# tailSensors.net
KiCad netlist of a schematic drawn in Altium Designer
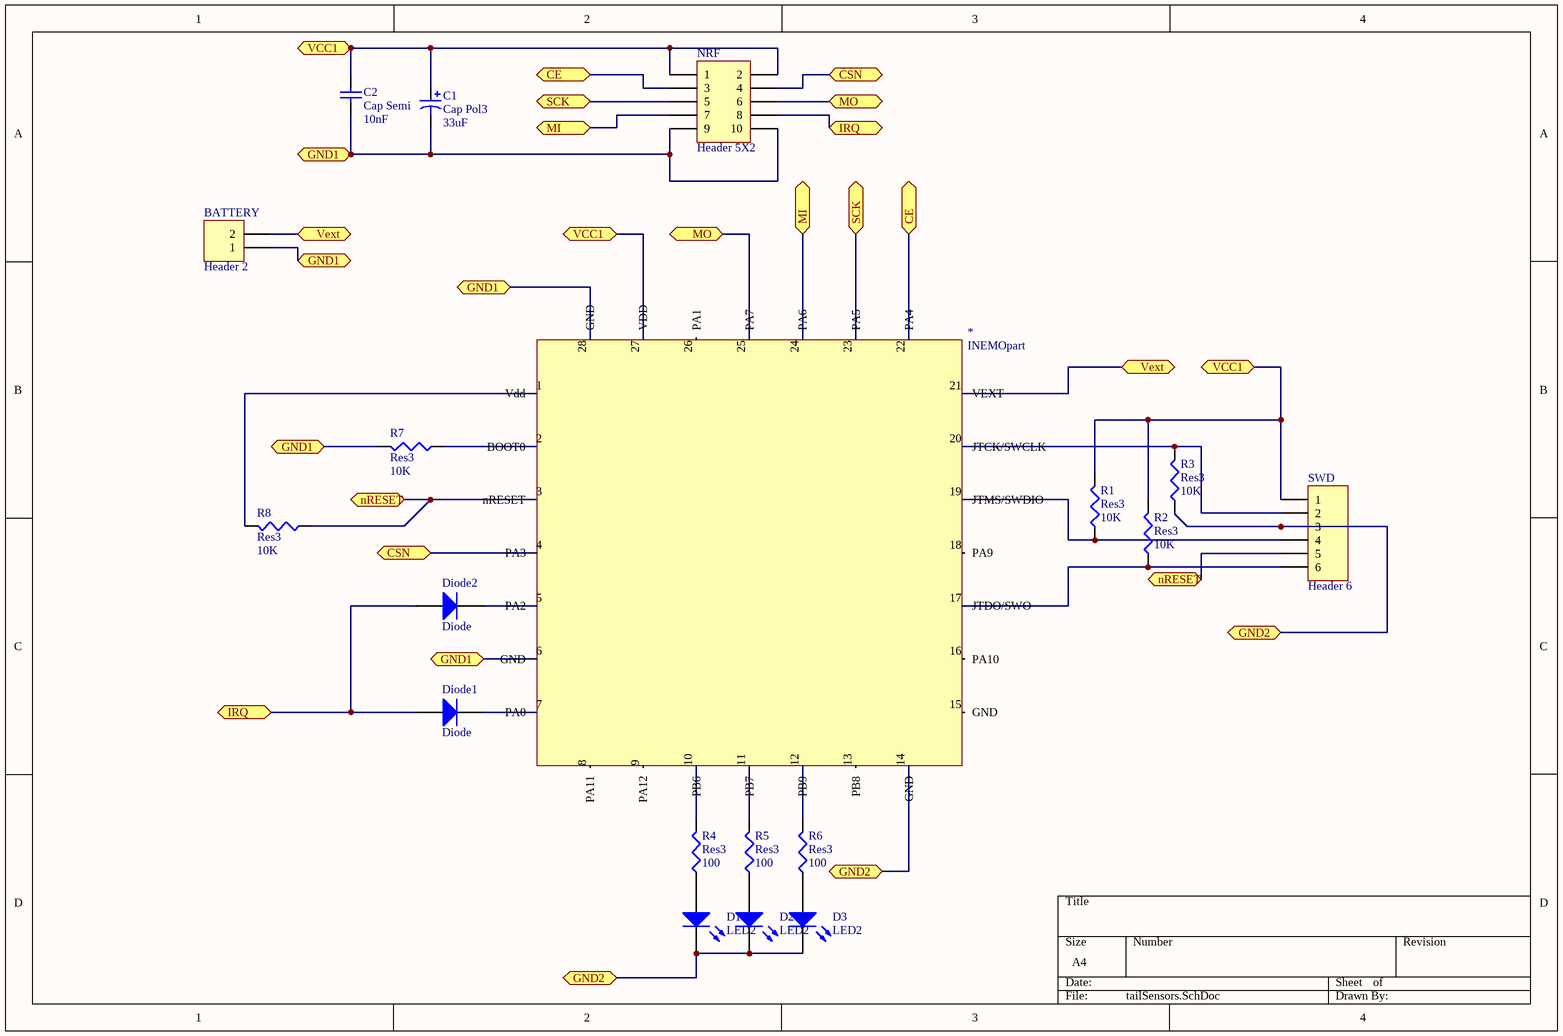
[diagram p0: tailSensors.SchDoc]

(export (version "E")
  (design (tool "Eeschema 10.0.6"))
  (components
    (comp (ref "*")
      (value "INEMOpart")
      (footprint "INEMO - duplicate3")
      (libsource (lib "INEMOLibrary") (part "Component_1"))
    )
    (comp (ref "BATTERY")
      (value "Header 2")
      (footprint "HDR1X2")
      (description "Header, 2-Pin")
      (fields (field (name "PUBLISHER") "Altium Limited"))
      (libsource (lib "Miscellaneous Connectors") (part "Header 2"))
    )
    (comp (ref "C1")
      (value "Cap Pol3")
      (footprint "C0805")
      (description "Polarized Capacitor (Surface Mount)")
      (fields (field (name "ALTIUM_VALUE") "33uF") (field (name "PUBLISHER") "Altium Limited"))
      (libsource (lib "Miscellaneous Devices") (part "Cap Pol3"))
    )
    (comp (ref "C2")
      (value "Cap Semi")
      (footprint "C1206")
      (description "Capacitor (Semiconductor SIM Model)")
      (fields (field (name "ALTIUM_VALUE") "10nF") (field (name "PUBLISHER") "Altium Limited"))
      (libsource (lib "Miscellaneous Devices") (part "Cap Semi"))
    )
    (comp (ref "D1")
      (value "LED2")
      (footprint "3.2X1.6X1.1")
      (description "Typical RED, GREEN, YELLOW, AMBER GaAs LED")
      (fields (field (name "PUBLISHER") "Altium Limited"))
      (libsource (lib "Miscellaneous Devices") (part "LED2"))
    )
    (comp (ref "D2")
      (value "LED2")
      (footprint "3.2X1.6X1.1")
      (description "Typical RED, GREEN, YELLOW, AMBER GaAs LED")
      (fields (field (name "PUBLISHER") "Altium Limited"))
      (libsource (lib "Miscellaneous Devices") (part "LED2"))
    )
    (comp (ref "D3")
      (value "LED2")
      (footprint "3.2X1.6X1.1")
      (description "Typical RED, GREEN, YELLOW, AMBER GaAs LED")
      (fields (field (name "PUBLISHER") "Altium Limited"))
      (libsource (lib "Miscellaneous Devices") (part "LED2"))
    )
    (comp (ref "Diode1")
      (value "Diode")
      (footprint "J1-0603")
      (description "Default Diode")
      (fields (field (name "PUBLISHER") "Altium Limited"))
      (libsource (lib "Miscellaneous Devices") (part "Diode"))
    )
    (comp (ref "Diode2")
      (value "Diode")
      (footprint "J1-0603")
      (description "Default Diode")
      (fields (field (name "PUBLISHER") "Altium Limited"))
      (libsource (lib "Miscellaneous Devices") (part "Diode"))
    )
    (comp (ref "NRF")
      (value "Header 5X2")
      (footprint "HDR2X5")
      (description "Header, 5-Pin, Dual row")
      (fields (field (name "PUBLISHER") "Altium Limited"))
      (libsource (lib "Miscellaneous Connectors") (part "Header 5X2"))
    )
    (comp (ref "R1")
      (value "Res3")
      (footprint "J1-0603")
      (description "Resistor")
      (fields (field (name "ALTIUM_VALUE") "10K") (field (name "PUBLISHER") "Altium Limited"))
      (libsource (lib "Miscellaneous Devices") (part "Res3"))
    )
    (comp (ref "R2")
      (value "Res3")
      (footprint "J1-0603")
      (description "Resistor")
      (fields (field (name "ALTIUM_VALUE") "10K") (field (name "PUBLISHER") "Altium Limited"))
      (libsource (lib "Miscellaneous Devices") (part "Res3"))
    )
    (comp (ref "R3")
      (value "Res3")
      (footprint "J1-0603")
      (description "Resistor")
      (fields (field (name "ALTIUM_VALUE") "10K") (field (name "PUBLISHER") "Altium Limited"))
      (libsource (lib "Miscellaneous Devices") (part "Res3"))
    )
    (comp (ref "R4")
      (value "Res3")
      (footprint "J1-0603")
      (description "Resistor")
      (fields (field (name "ALTIUM_VALUE") "100") (field (name "PUBLISHER") "Altium Limited"))
      (libsource (lib "Miscellaneous Devices") (part "Res3"))
    )
    (comp (ref "R5")
      (value "Res3")
      (footprint "J1-0603")
      (description "Resistor")
      (fields (field (name "ALTIUM_VALUE") "100") (field (name "PUBLISHER") "Altium Limited"))
      (libsource (lib "Miscellaneous Devices") (part "Res3"))
    )
    (comp (ref "R6")
      (value "Res3")
      (footprint "J1-0603")
      (description "Resistor")
      (fields (field (name "ALTIUM_VALUE") "100") (field (name "PUBLISHER") "Altium Limited"))
      (libsource (lib "Miscellaneous Devices") (part "Res3"))
    )
    (comp (ref "R7")
      (value "Res3")
      (footprint "J1-0603")
      (description "Resistor")
      (fields (field (name "ALTIUM_VALUE") "10K") (field (name "PUBLISHER") "Altium Limited"))
      (libsource (lib "Miscellaneous Devices") (part "Res3"))
    )
    (comp (ref "R8")
      (value "Res3")
      (footprint "J1-0603")
      (description "Resistor")
      (fields (field (name "ALTIUM_VALUE") "10K") (field (name "PUBLISHER") "Altium Limited"))
      (libsource (lib "Miscellaneous Devices") (part "Res3"))
    )
    (comp (ref "SWD")
      (value "Header 6")
      (footprint "HDR1X6")
      (description "Header, 6-Pin")
      (fields (field (name "PUBLISHER") "Altium Limited"))
      (libsource (lib "Miscellaneous Connectors") (part "Header 6"))
    )
  )
  (nets
    (net (code "1") (name "/CE") (class "Default")
      (node (ref "*") (pin "22") (pinfunction "PA4_22") (pintype "passive"))
      (node (ref "NRF") (pin "3") (pinfunction "3_3") (pintype "passive"))
    )
    (net (code "2") (name "/CSN") (class "Default")
      (node (ref "*") (pin "4") (pinfunction "PA3_4") (pintype "passive"))
      (node (ref "NRF") (pin "4") (pinfunction "4_4") (pintype "passive"))
    )
    (net (code "3") (name "/GND1") (class "Default")
      (node (ref "*") (pin "28") (pinfunction "GND_28") (pintype "passive"))
      (node (ref "*") (pin "6") (pinfunction "GND_6") (pintype "passive"))
      (node (ref "BATTERY") (pin "1") (pinfunction "1_1") (pintype "passive"))
      (node (ref "C1") (pin "2") (pinfunction "2_2") (pintype "passive"))
      (node (ref "C2") (pin "1") (pinfunction "1_1") (pintype "passive"))
      (node (ref "NRF") (pin "10") (pinfunction "10_10") (pintype "passive"))
      (node (ref "NRF") (pin "9") (pinfunction "9_9") (pintype "passive"))
      (node (ref "R7") (pin "2") (pinfunction "2_2") (pintype "passive"))
    )
    (net (code "4") (name "/GND2") (class "Default")
      (node (ref "*") (pin "14") (pinfunction "GND_14") (pintype "passive"))
      (node (ref "D1") (pin "2") (pinfunction "K_2") (pintype "passive"))
      (node (ref "D2") (pin "2") (pinfunction "K_2") (pintype "passive"))
      (node (ref "D3") (pin "2") (pinfunction "K_2") (pintype "passive"))
      (node (ref "R3") (pin "1") (pinfunction "1_1") (pintype "passive"))
      (node (ref "SWD") (pin "3") (pinfunction "3_3") (pintype "passive"))
    )
    (net (code "5") (name "/IRQ") (class "Default")
      (node (ref "Diode1") (pin "1") (pinfunction "A_1") (pintype "passive"))
      (node (ref "Diode2") (pin "1") (pinfunction "A_1") (pintype "passive"))
      (node (ref "NRF") (pin "8") (pinfunction "8_8") (pintype "passive"))
    )
    (net (code "6") (name "/MI") (class "Default")
      (node (ref "*") (pin "24") (pinfunction "PA6_24") (pintype "passive"))
      (node (ref "NRF") (pin "7") (pinfunction "7_7") (pintype "passive"))
    )
    (net (code "7") (name "/MO") (class "Default")
      (node (ref "*") (pin "25") (pinfunction "PA7_25") (pintype "passive"))
      (node (ref "NRF") (pin "6") (pinfunction "6_6") (pintype "passive"))
    )
    (net (code "8") (name "/SCK") (class "Default")
      (node (ref "*") (pin "23") (pinfunction "PA5_23") (pintype "passive"))
      (node (ref "NRF") (pin "5") (pinfunction "5_5") (pintype "passive"))
    )
    (net (code "9") (name "/VCC1") (class "Default")
      (node (ref "*") (pin "27") (pinfunction "VDD_27") (pintype "passive"))
      (node (ref "C1") (pin "1") (pinfunction "1_1") (pintype "passive"))
      (node (ref "C2") (pin "2") (pinfunction "2_2") (pintype "passive"))
      (node (ref "NRF") (pin "1") (pinfunction "1_1") (pintype "passive"))
      (node (ref "NRF") (pin "2") (pinfunction "2_2") (pintype "passive"))
      (node (ref "R1") (pin "2") (pinfunction "2_2") (pintype "passive"))
      (node (ref "R2") (pin "2") (pinfunction "2_2") (pintype "passive"))
      (node (ref "SWD") (pin "1") (pinfunction "1_1") (pintype "passive"))
    )
    (net (code "10") (name "/Vext") (class "Default")
      (node (ref "*") (pin "21") (pinfunction "VEXT_21") (pintype "passive"))
      (node (ref "BATTERY") (pin "2") (pinfunction "2_2") (pintype "passive"))
    )
    (net (code "11") (name "/nRESET") (class "Default")
      (node (ref "*") (pin "3") (pinfunction "nRESET_3") (pintype "passive"))
      (node (ref "R8") (pin "1") (pinfunction "1_1") (pintype "passive"))
      (node (ref "SWD") (pin "5") (pinfunction "5_5") (pintype "passive"))
    )
    (net (code "12") (name "Net-(*-BOOT0)") (class "Default")
      (node (ref "*") (pin "2") (pinfunction "BOOT0_2") (pintype "passive"))
      (node (ref "R7") (pin "1") (pinfunction "1_1") (pintype "passive"))
    )
    (net (code "13") (name "Net-(*-JTCK{slash}SWCLK)") (class "Default")
      (node (ref "*") (pin "20") (pinfunction "JTCK/SWCLK_20") (pintype "passive"))
      (node (ref "R3") (pin "2") (pinfunction "2_2") (pintype "passive"))
      (node (ref "SWD") (pin "2") (pinfunction "2_2") (pintype "passive"))
    )
    (net (code "14") (name "Net-(*-JTDO{slash}SWO)") (class "Default")
      (node (ref "*") (pin "17") (pinfunction "JTDO/SWO_17") (pintype "passive"))
      (node (ref "R2") (pin "1") (pinfunction "1_1") (pintype "passive"))
      (node (ref "SWD") (pin "6") (pinfunction "6_6") (pintype "passive"))
    )
    (net (code "15") (name "Net-(*-JTMS{slash}SWDIO)") (class "Default")
      (node (ref "*") (pin "19") (pinfunction "JTMS/SWDIO_19") (pintype "passive"))
      (node (ref "R1") (pin "1") (pinfunction "1_1") (pintype "passive"))
      (node (ref "SWD") (pin "4") (pinfunction "4_4") (pintype "passive"))
    )
    (net (code "16") (name "Net-(*-PA0)") (class "Default")
      (node (ref "*") (pin "7") (pinfunction "PA0_7") (pintype "passive"))
      (node (ref "Diode1") (pin "2") (pinfunction "K_2") (pintype "passive"))
    )
    (net (code "17") (name "Net-(*-PA2)") (class "Default")
      (node (ref "*") (pin "5") (pinfunction "PA2_5") (pintype "passive"))
      (node (ref "Diode2") (pin "2") (pinfunction "K_2") (pintype "passive"))
    )
    (net (code "18") (name "Net-(*-PB6)") (class "Default")
      (node (ref "*") (pin "10") (pinfunction "PB6_10") (pintype "passive"))
      (node (ref "R4") (pin "2") (pinfunction "2_2") (pintype "passive"))
    )
    (net (code "19") (name "Net-(*-PB7)") (class "Default")
      (node (ref "*") (pin "11") (pinfunction "PB7_11") (pintype "passive"))
      (node (ref "R5") (pin "2") (pinfunction "2_2") (pintype "passive"))
    )
    (net (code "20") (name "Net-(*-PB9)") (class "Default")
      (node (ref "*") (pin "12") (pinfunction "PB9_12") (pintype "passive"))
      (node (ref "R6") (pin "2") (pinfunction "2_2") (pintype "passive"))
    )
    (net (code "21") (name "Net-(*-Vdd)") (class "Default")
      (node (ref "*") (pin "1") (pinfunction "Vdd_1") (pintype "passive"))
      (node (ref "R8") (pin "2") (pinfunction "2_2") (pintype "passive"))
    )
    (net (code "22") (name "Net-(D1-A)") (class "Default")
      (node (ref "D1") (pin "1") (pinfunction "A_1") (pintype "passive"))
      (node (ref "R4") (pin "1") (pinfunction "1_1") (pintype "passive"))
    )
    (net (code "23") (name "Net-(D2-A)") (class "Default")
      (node (ref "D2") (pin "1") (pinfunction "A_1") (pintype "passive"))
      (node (ref "R5") (pin "1") (pinfunction "1_1") (pintype "passive"))
    )
    (net (code "24") (name "Net-(D3-A)") (class "Default")
      (node (ref "D3") (pin "1") (pinfunction "A_1") (pintype "passive"))
      (node (ref "R6") (pin "1") (pinfunction "1_1") (pintype "passive"))
    )
    (net (code "25") (name "unconnected-(*-GND-Pad15)") (class "Default")
      (node (ref "*") (pin "15") (pinfunction "GND_15") (pintype "passive"))
    )
    (net (code "26") (name "unconnected-(*-PA1-Pad26)") (class "Default")
      (node (ref "*") (pin "26") (pinfunction "PA1_26") (pintype "passive"))
    )
    (net (code "27") (name "unconnected-(*-PA9-Pad18)") (class "Default")
      (node (ref "*") (pin "18") (pinfunction "PA9_18") (pintype "passive"))
    )
    (net (code "28") (name "unconnected-(*-PA10-Pad16)") (class "Default")
      (node (ref "*") (pin "16") (pinfunction "PA10_16") (pintype "passive"))
    )
    (net (code "29") (name "unconnected-(*-PA11-Pad8)") (class "Default")
      (node (ref "*") (pin "8") (pinfunction "PA11_8") (pintype "passive"))
    )
    (net (code "30") (name "unconnected-(*-PA12-Pad9)") (class "Default")
      (node (ref "*") (pin "9") (pinfunction "PA12_9") (pintype "passive"))
    )
    (net (code "31") (name "unconnected-(*-PB8-Pad13)") (class "Default")
      (node (ref "*") (pin "13") (pinfunction "PB8_13") (pintype "passive"))
    )
  )
)
